# seed_sentinel.net
KiCad netlist of a schematic drawn in Altium Designer
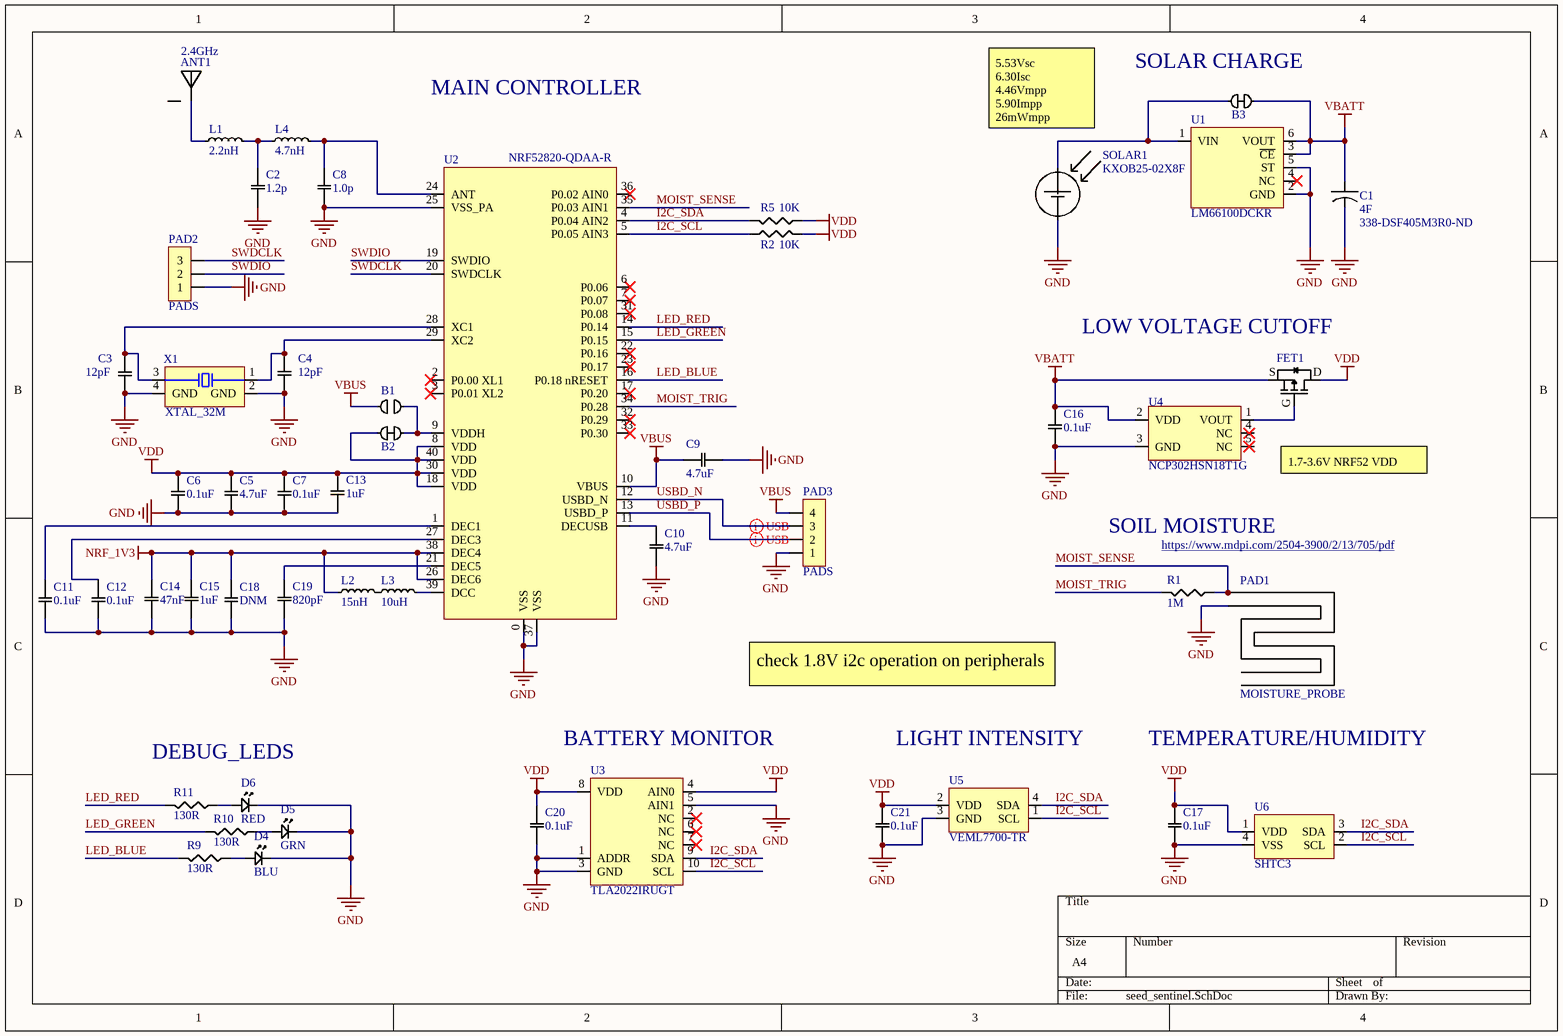
[diagram p0: seed_sentinel.SchDoc]

(export (version "E")
  (design (tool "Eeschema 10.0.6"))
  (components
    (comp (ref "ANT1")
      (value "2.4GHz")
      (footprint "ANT_RFANT5220110A2T")
      (description "2.4GHz chip antenna")
      (libsource (lib "seed_sentinel") (part "ANT_2G4_CHIP_RFANT5220110A2T"))
    )
    (comp (ref "B1")
      (value "SOLDER_BRIDGE_NO")
      (footprint "SOLDER_BRIDGE_NO")
      (libsource (lib "seed_sentinel") (part "SOLDER_BRIDGE_NO"))
    )
    (comp (ref "B2")
      (value "SOLDER_BRIDGE_C")
      (footprint "SOLDER_BRIDGE_NC")
      (libsource (lib "seed_sentinel") (part "SOLDER_BRIDGE_NC"))
    )
    (comp (ref "B3")
      (value "SOLDER_BRIDGE_C")
      (footprint "SOLDER_BRIDGE_NC")
      (libsource (lib "seed_sentinel") (part "SOLDER_BRIDGE_NC"))
    )
    (comp (ref "C1")
      (value "4F")
      (footprint "CAP_8mm")
      (description "4F 3V supercap")
      (fields (field (name "SUPPLIER PART NUMBER 1") "338-DSF405M3R0-ND"))
      (libsource (lib "seed_sentinel") (part "CAP_4_THRU"))
    )
    (comp (ref "C2")
      (value "1.2p")
      (footprint "CHIP_0402")
      (description "1.2pF RF capacitor")
      (libsource (lib "seed_sentinel") (part "CAP_1.2p_0402"))
    )
    (comp (ref "C3")
      (value "12pF")
      (footprint "CHIP_0402")
      (description "12pF NP0 0603 Capacitor")
      (libsource (lib "seed_sentinel") (part "CAP_12p_0402"))
    )
    (comp (ref "C4")
      (value "12pF")
      (footprint "CHIP_0402")
      (description "12pF NP0 0603 Capacitor")
      (libsource (lib "seed_sentinel") (part "CAP_12p_0402"))
    )
    (comp (ref "C5")
      (value "4.7uF")
      (footprint "CHIP_0402")
      (description "4.7uF 0603 6.3V")
      (libsource (lib "seed_sentinel") (part "CAP_4.7u_0402"))
    )
    (comp (ref "C6")
      (value "0.1uF")
      (footprint "CHIP_0402")
      (description "0.1uF X7R 0805 Capacitor")
      (libsource (lib "seed_sentinel") (part "CAP_100p_0402"))
    )
    (comp (ref "C7")
      (value "0.1uF")
      (footprint "CHIP_0402")
      (description "0.1uF X7R 0805 Capacitor")
      (libsource (lib "seed_sentinel") (part "CAP_100p_0402"))
    )
    (comp (ref "C8")
      (value "1.0p")
      (footprint "CHIP_0402")
      (description "1.0pF RF capacitor")
      (libsource (lib "seed_sentinel") (part "CAP_1.0p_0402"))
    )
    (comp (ref "C9")
      (value "4.7uF")
      (footprint "CHIP_0402")
      (description "4.7uF 0603 6.3V")
      (libsource (lib "seed_sentinel") (part "CAP_4.7u_0402"))
    )
    (comp (ref "C10")
      (value "4.7uF")
      (footprint "CHIP_0402")
      (description "4.7uF 0603 6.3V")
      (libsource (lib "seed_sentinel") (part "CAP_4.7u_0402"))
    )
    (comp (ref "C11")
      (value "0.1uF")
      (footprint "CHIP_0402")
      (description "0.1uF X7R 0805 Capacitor")
      (libsource (lib "seed_sentinel") (part "CAP_100p_0402"))
    )
    (comp (ref "C12")
      (value "0.1uF")
      (footprint "CHIP_0402")
      (description "0.1uF X7R 0805 Capacitor")
      (libsource (lib "seed_sentinel") (part "CAP_100p_0402"))
    )
    (comp (ref "C13")
      (value "1uF")
      (footprint "CHIP_0402")
      (libsource (lib "seed_sentinel") (part "CAP_1u_0402"))
    )
    (comp (ref "C14")
      (value "47nF")
      (footprint "CHIP_0402")
      (description "47nF 0603 6.3V")
      (libsource (lib "seed_sentinel") (part "CAP_47n_0402"))
    )
    (comp (ref "C15")
      (value "1uF")
      (footprint "CHIP_0402")
      (libsource (lib "seed_sentinel") (part "CAP_1u_0402"))
    )
    (comp (ref "C16")
      (value "0.1uF")
      (footprint "CHIP_0402")
      (description "0.1uF X7R 0805 Capacitor")
      (libsource (lib "seed_sentinel") (part "CAP_100p_0402"))
    )
    (comp (ref "C17")
      (value "0.1uF")
      (footprint "CHIP_0402")
      (description "0.1uF X7R 0805 Capacitor")
      (libsource (lib "seed_sentinel") (part "CAP_100p_0402"))
    )
    (comp (ref "C18")
      (value "DNM")
      (footprint "CHIP_0402")
      (libsource (lib "seed_sentinel") (part "CAP_DNM_0402"))
    )
    (comp (ref "C19")
      (value "820pF")
      (footprint "CHIP_0402")
      (description "820pF X7R 0805 Capacitor")
      (libsource (lib "seed_sentinel") (part "CAP_820p_0402"))
    )
    (comp (ref "C20")
      (value "0.1uF")
      (footprint "CHIP_0402")
      (description "0.1uF X7R 0805 Capacitor")
      (libsource (lib "seed_sentinel") (part "CAP_100p_0402"))
    )
    (comp (ref "C21")
      (value "0.1uF")
      (footprint "CHIP_0402")
      (description "0.1uF X7R 0805 Capacitor")
      (libsource (lib "seed_sentinel") (part "CAP_100p_0402"))
    )
    (comp (ref "D4")
      (value "BLU")
      (footprint "LED_0402")
      (libsource (lib "seed_sentinel") (part "LED_BLU_0402"))
    )
    (comp (ref "D5")
      (value "GRN")
      (footprint "LED_0402")
      (libsource (lib "seed_sentinel") (part "LED_GRN_0402"))
    )
    (comp (ref "D6")
      (value "RED")
      (footprint "LED_0402")
      (libsource (lib "seed_sentinel") (part "LED_RED_0402"))
    )
    (comp (ref "FET1")
      (value "RV2C014BCT2CL")
      (footprint "DFN1006-3")
      (libsource (lib "seed_sentinel") (part "FET_20V_200mA"))
    )
    (comp (ref "L1")
      (value "2.2nH")
      (footprint "CHIP_0402")
      (description "2.2nH high frequency")
      (libsource (lib "seed_sentinel") (part "IND_2.2n_0402"))
    )
    (comp (ref "L2")
      (value "15nH")
      (footprint "CHIP_0402")
      (description "15nH chip inductor")
      (libsource (lib "seed_sentinel") (part "IND_15n_0402"))
    )
    (comp (ref "L3")
      (value "10uH")
      (footprint "CHIP_0603")
      (description "10uH chip inductor")
      (libsource (lib "seed_sentinel") (part "IND_10u_0402"))
    )
    (comp (ref "L4")
      (value "4.7nH")
      (footprint "CHIP_0402")
      (description "4.7nH high frequency")
      (libsource (lib "seed_sentinel") (part "IND_4.7n_0402"))
    )
    (comp (ref "PAD1")
      (value "MOISTURE_PROBE")
      (footprint "MOIST_CAP")
      (libsource (lib "seed_sentinel") (part "MOISTURE_PROBE"))
    )
    (comp (ref "PAD2")
      (value "PADS")
      (footprint "CON_PADS_3")
      (libsource (lib "seed_sentinel") (part "CON_PADS_3"))
    )
    (comp (ref "PAD3")
      (value "PADS")
      (footprint "CON_PADS_4")
      (libsource (lib "seed_sentinel") (part "CON_PADS_4"))
    )
    (comp (ref "R1")
      (value "1M")
      (footprint "CHIP_0402")
      (description "1Mohm")
      (libsource (lib "seed_sentinel") (part "RES_1M_0402"))
    )
    (comp (ref "R2")
      (value "10K")
      (footprint "CHIP_0402")
      (description "10Kohm")
      (libsource (lib "seed_sentinel") (part "RES_10K_0402"))
    )
    (comp (ref "R5")
      (value "10K")
      (footprint "CHIP_0402")
      (description "10Kohm")
      (libsource (lib "seed_sentinel") (part "RES_10K_0402"))
    )
    (comp (ref "R9")
      (value "130R")
      (footprint "CHIP_0402")
      (description "130ohm")
      (libsource (lib "seed_sentinel") (part "RES_130R_0402"))
    )
    (comp (ref "R10")
      (value "130R")
      (footprint "CHIP_0402")
      (description "130ohm")
      (libsource (lib "seed_sentinel") (part "RES_130R_0402"))
    )
    (comp (ref "R11")
      (value "130R")
      (footprint "CHIP_0402")
      (description "130ohm")
      (libsource (lib "seed_sentinel") (part "RES_130R_0402"))
    )
    (comp (ref "SOLAR1")
      (value "KXOB25-02X8F")
      (footprint "SOLAR")
      (description "26.3mW 6.3mA 5.53V")
      (libsource (lib "seed_sentinel") (part "SOLAR_5V5_6m3"))
    )
    (comp (ref "U1")
      (value "LM66100DCKR")
      (footprint "SC70-6")
      (description "Ideal diode")
      (libsource (lib "seed_sentinel") (part "DIO_IDEAL"))
    )
    (comp (ref "U2")
      (value "NRF52820-QDAA-R")
      (footprint "QFN40 5x5")
      (libsource (lib "seed_sentinel") (part "NRF52820-QDAA-R"))
    )
    (comp (ref "U3")
      (value "TLA2022IRUGT")
      (footprint "RQFP_10")
      (libsource (lib "seed_sentinel") (part "SEN_ADC_TLA2022IRUGT"))
    )
    (comp (ref "U4")
      (value "NCP302HSN18T1G")
      (footprint "TSOP-5")
      (description "1.8V low voltage cutoff")
      (libsource (lib "seed_sentinel") (part "LVC_1.8V"))
    )
    (comp (ref "U5")
      (value "VEML7700-TR")
      (footprint "VEML7700")
      (libsource (lib "seed_sentinel") (part "SEN_LIGHT_VEML7700"))
    )
    (comp (ref "U6")
      (value "SHTC3")
      (footprint "SHTC3")
      (libsource (lib "seed_sentinel") (part "SEN_TEMP_HUMID_SHTC3"))
    )
    (comp (ref "X1")
      (value "XTAL_32M")
      (footprint "ECS-320")
      (libsource (lib "seed_sentinel") (part "XTAL_32M"))
    )
  )
  (nets
    (net (code "1") (name "/I2C_SCL") (class "Default")
      (node (ref "R2") (pin "1") (pinfunction "1_1") (pintype "passive"))
      (node (ref "U2") (pin "5") (pinfunction "P0.05_AIN3_5") (pintype "passive"))
      (node (ref "U3") (pin "10") (pinfunction "SCL_10") (pintype "passive"))
      (node (ref "U5") (pin "1") (pinfunction "SCL_1") (pintype "passive"))
      (node (ref "U6") (pin "2") (pinfunction "SCL_2") (pintype "passive"))
    )
    (net (code "2") (name "/I2C_SDA") (class "Default")
      (node (ref "R5") (pin "2") (pinfunction "2_2") (pintype "passive"))
      (node (ref "U2") (pin "4") (pinfunction "P0.04_AIN2_4") (pintype "passive"))
      (node (ref "U3") (pin "9") (pinfunction "SDA_9") (pintype "passive"))
      (node (ref "U5") (pin "4") (pinfunction "SDA_4") (pintype "passive"))
      (node (ref "U6") (pin "3") (pinfunction "SDA_3") (pintype "passive"))
    )
    (net (code "3") (name "/LED_BLUE") (class "Default")
      (node (ref "R9") (pin "2") (pinfunction "2_2") (pintype "passive"))
      (node (ref "U2") (pin "16") (pinfunction "P0.18_nRESET_16") (pintype "passive"))
    )
    (net (code "4") (name "/LED_GREEN") (class "Default")
      (node (ref "R10") (pin "2") (pinfunction "2_2") (pintype "passive"))
      (node (ref "U2") (pin "15") (pinfunction "P0.15_15") (pintype "passive"))
    )
    (net (code "5") (name "/LED_RED") (class "Default")
      (node (ref "R11") (pin "2") (pinfunction "2_2") (pintype "passive"))
      (node (ref "U2") (pin "14") (pinfunction "P0.14_14") (pintype "passive"))
    )
    (net (code "6") (name "/MOIST_SENSE") (class "Default")
      (node (ref "PAD1") (pin "1") (pinfunction "1_1") (pintype "passive"))
      (node (ref "R1") (pin "1") (pinfunction "1_1") (pintype "passive"))
      (node (ref "U2") (pin "35") (pinfunction "P0.03_AIN1_35") (pintype "passive"))
    )
    (net (code "7") (name "/MOIST_TRIG") (class "Default")
      (node (ref "R1") (pin "2") (pinfunction "2_2") (pintype "passive"))
      (node (ref "U2") (pin "34") (pinfunction "P0.28_34") (pintype "passive"))
    )
    (net (code "8") (name "/SWDCLK") (class "Default")
      (node (ref "PAD2") (pin "3") (pinfunction "3_3") (pintype "passive"))
      (node (ref "U2") (pin "20") (pinfunction "SWDCLK_20") (pintype "passive"))
    )
    (net (code "9") (name "/SWDIO") (class "Default")
      (node (ref "PAD2") (pin "2") (pinfunction "2_2") (pintype "passive"))
      (node (ref "U2") (pin "19") (pinfunction "SWDIO_19") (pintype "passive"))
    )
    (net (code "10") (name "/USBD_N") (class "Default")
      (node (ref "PAD3") (pin "3") (pinfunction "3_3") (pintype "passive"))
      (node (ref "U2") (pin "12") (pinfunction "USBD_N_12") (pintype "passive"))
    )
    (net (code "11") (name "/USBD_P") (class "Default")
      (node (ref "PAD3") (pin "2") (pinfunction "2_2") (pintype "passive"))
      (node (ref "U2") (pin "13") (pinfunction "USBD_P_13") (pintype "passive"))
    )
    (net (code "12") (name "GND") (class "Default")
      (node (ref "C1") (pin "-") (pinfunction "-_-") (pintype "passive"))
      (node (ref "C10") (pin "2") (pinfunction "2_2") (pintype "passive"))
      (node (ref "C11") (pin "2") (pinfunction "2_2") (pintype "passive"))
      (node (ref "C12") (pin "2") (pinfunction "2_2") (pintype "passive"))
      (node (ref "C13") (pin "1") (pinfunction "1_1") (pintype "passive"))
      (node (ref "C14") (pin "1") (pinfunction "1_1") (pintype "passive"))
      (node (ref "C15") (pin "1") (pinfunction "1_1") (pintype "passive"))
      (node (ref "C16") (pin "2") (pinfunction "2_2") (pintype "passive"))
      (node (ref "C17") (pin "2") (pinfunction "2_2") (pintype "passive"))
      (node (ref "C18") (pin "2") (pinfunction "2_2") (pintype "passive"))
      (node (ref "C19") (pin "1") (pinfunction "1_1") (pintype "passive"))
      (node (ref "C2") (pin "1") (pinfunction "1_1") (pintype "passive"))
      (node (ref "C20") (pin "2") (pinfunction "2_2") (pintype "passive"))
      (node (ref "C21") (pin "2") (pinfunction "2_2") (pintype "passive"))
      (node (ref "C3") (pin "2") (pinfunction "2_2") (pintype "passive"))
      (node (ref "C4") (pin "1") (pinfunction "1_1") (pintype "passive"))
      (node (ref "C5") (pin "2") (pinfunction "2_2") (pintype "passive"))
      (node (ref "C6") (pin "2") (pinfunction "2_2") (pintype "passive"))
      (node (ref "C7") (pin "2") (pinfunction "2_2") (pintype "passive"))
      (node (ref "C8") (pin "1") (pinfunction "1_1") (pintype "passive"))
      (node (ref "C9") (pin "2") (pinfunction "2_2") (pintype "passive"))
      (node (ref "D4") (pin "C") (pinfunction "C_C") (pintype "passive"))
      (node (ref "D5") (pin "C") (pinfunction "C_C") (pintype "passive"))
      (node (ref "D6") (pin "C") (pinfunction "C_C") (pintype "passive"))
      (node (ref "PAD1") (pin "2") (pinfunction "2_2") (pintype "passive"))
      (node (ref "PAD2") (pin "1") (pinfunction "1_1") (pintype "passive"))
      (node (ref "PAD3") (pin "1") (pinfunction "1_1") (pintype "passive"))
      (node (ref "SOLAR1") (pin "-") (pinfunction "-_-") (pintype "passive"))
      (node (ref "U1") (pin "2") (pinfunction "GND_2") (pintype "passive"))
      (node (ref "U1") (pin "5") (pinfunction "ST_5") (pintype "passive"))
      (node (ref "U2") (pin "0") (pinfunction "VSS_0") (pintype "passive"))
      (node (ref "U2") (pin "25") (pinfunction "VSS_PA_25") (pintype "passive"))
      (node (ref "U2") (pin "37") (pinfunction "VSS_37") (pintype "passive"))
      (node (ref "U3") (pin "1") (pinfunction "ADDR_1") (pintype "passive"))
      (node (ref "U3") (pin "3") (pinfunction "GND_3") (pintype "passive"))
      (node (ref "U3") (pin "5") (pinfunction "AIN1_5") (pintype "passive"))
      (node (ref "U4") (pin "3") (pinfunction "GND_3") (pintype "passive"))
      (node (ref "U5") (pin "3") (pinfunction "GND_3") (pintype "passive"))
      (node (ref "U6") (pin "4") (pinfunction "VSS_4") (pintype "passive"))
      (node (ref "X1") (pin "2") (pinfunction "GND_2") (pintype "passive"))
      (node (ref "X1") (pin "4") (pinfunction "GND_4") (pintype "passive"))
    )
    (net (code "13") (name "NRF_1V3") (class "Default")
      (node (ref "C14") (pin "2") (pinfunction "2_2") (pintype "passive"))
      (node (ref "C15") (pin "2") (pinfunction "2_2") (pintype "passive"))
      (node (ref "C18") (pin "1") (pinfunction "1_1") (pintype "passive"))
      (node (ref "L2") (pin "1") (pinfunction "1_1") (pintype "passive"))
      (node (ref "U2") (pin "26") (pinfunction "DEC6_26") (pintype "passive"))
      (node (ref "U2") (pin "38") (pinfunction "DEC4_38") (pintype "passive"))
    )
    (net (code "14") (name "Net-(ANT1-PadIN)") (class "Default")
      (node (ref "ANT1") (pin "IN") (pinfunction "IN_IN") (pintype "passive"))
      (node (ref "L1") (pin "1") (pinfunction "1_1") (pintype "passive"))
    )
    (net (code "15") (name "Net-(C2-Pad2)") (class "Default")
      (node (ref "C2") (pin "2") (pinfunction "2_2") (pintype "passive"))
      (node (ref "L1") (pin "2") (pinfunction "2_2") (pintype "passive"))
      (node (ref "L4") (pin "1") (pinfunction "1_1") (pintype "passive"))
    )
    (net (code "16") (name "Net-(D4-PadA)") (class "Default")
      (node (ref "D4") (pin "A") (pinfunction "A_A") (pintype "passive"))
      (node (ref "R9") (pin "1") (pinfunction "1_1") (pintype "passive"))
    )
    (net (code "17") (name "Net-(D5-PadA)") (class "Default")
      (node (ref "D5") (pin "A") (pinfunction "A_A") (pintype "passive"))
      (node (ref "R10") (pin "1") (pinfunction "1_1") (pintype "passive"))
    )
    (net (code "18") (name "Net-(D6-PadA)") (class "Default")
      (node (ref "D6") (pin "A") (pinfunction "A_A") (pintype "passive"))
      (node (ref "R11") (pin "1") (pinfunction "1_1") (pintype "passive"))
    )
    (net (code "19") (name "Net-(L2-Pad2)") (class "Default")
      (node (ref "L2") (pin "2") (pinfunction "2_2") (pintype "passive"))
      (node (ref "L3") (pin "1") (pinfunction "1_1") (pintype "passive"))
    )
    (net (code "20") (name "Net-(U1-VIN)") (class "Default")
      (node (ref "B3") (pin "1") (pinfunction "1_1") (pintype "passive"))
      (node (ref "SOLAR1") (pin "+") (pinfunction "+_+") (pintype "passive"))
      (node (ref "U1") (pin "1") (pinfunction "VIN_1") (pintype "passive"))
    )
    (net (code "21") (name "Net-(U2-ANT)") (class "Default")
      (node (ref "C8") (pin "2") (pinfunction "2_2") (pintype "passive"))
      (node (ref "L4") (pin "2") (pinfunction "2_2") (pintype "passive"))
      (node (ref "U2") (pin "24") (pinfunction "ANT_24") (pintype "passive"))
    )
    (net (code "22") (name "Net-(U2-DCC)") (class "Default")
      (node (ref "L3") (pin "2") (pinfunction "2_2") (pintype "passive"))
      (node (ref "U2") (pin "39") (pinfunction "DCC_39") (pintype "passive"))
    )
    (net (code "23") (name "Net-(U2-DEC1)") (class "Default")
      (node (ref "C11") (pin "1") (pinfunction "1_1") (pintype "passive"))
      (node (ref "U2") (pin "1") (pinfunction "DEC1_1") (pintype "passive"))
    )
    (net (code "24") (name "Net-(U2-DEC3)") (class "Default")
      (node (ref "C12") (pin "1") (pinfunction "1_1") (pintype "passive"))
      (node (ref "U2") (pin "27") (pinfunction "DEC3_27") (pintype "passive"))
    )
    (net (code "25") (name "Net-(U2-DEC5)") (class "Default")
      (node (ref "C19") (pin "2") (pinfunction "2_2") (pintype "passive"))
      (node (ref "U2") (pin "21") (pinfunction "DEC5_21") (pintype "passive"))
    )
    (net (code "26") (name "Net-(U2-DECUSB)") (class "Default")
      (node (ref "C10") (pin "1") (pinfunction "1_1") (pintype "passive"))
      (node (ref "U2") (pin "11") (pinfunction "DECUSB_11") (pintype "passive"))
    )
    (net (code "27") (name "Net-(U2-VDDH)") (class "Default")
      (node (ref "B1") (pin "1") (pinfunction "1_1") (pintype "passive"))
      (node (ref "B2") (pin "2") (pinfunction "2_2") (pintype "passive"))
      (node (ref "U2") (pin "9") (pinfunction "VDDH_9") (pintype "passive"))
    )
    (net (code "28") (name "Net-(U2-XC1)") (class "Default")
      (node (ref "C3") (pin "1") (pinfunction "1_1") (pintype "passive"))
      (node (ref "U2") (pin "28") (pinfunction "XC1_28") (pintype "passive"))
      (node (ref "X1") (pin "3") (pintype "passive"))
    )
    (net (code "29") (name "Net-(U2-XC2)") (class "Default")
      (node (ref "C4") (pin "2") (pinfunction "2_2") (pintype "passive"))
      (node (ref "U2") (pin "29") (pinfunction "XC2_29") (pintype "passive"))
      (node (ref "X1") (pin "1") (pintype "passive"))
    )
    (net (code "30") (name "Net-(U4-VOUT)") (class "Default")
      (node (ref "FET1") (pin "G") (pinfunction "G_G") (pintype "passive"))
      (node (ref "U4") (pin "1") (pinfunction "VOUT_1") (pintype "passive"))
    )
    (net (code "31") (name "VBATT") (class "Default")
      (node (ref "B3") (pin "2") (pinfunction "2_2") (pintype "passive"))
      (node (ref "C1") (pin "+") (pinfunction "+_+") (pintype "passive"))
      (node (ref "C16") (pin "1") (pinfunction "1_1") (pintype "passive"))
      (node (ref "FET1") (pin "S") (pinfunction "S_S") (pintype "passive"))
      (node (ref "U1") (pin "3") (pinfunction "~{CE}_3") (pintype "passive"))
      (node (ref "U1") (pin "6") (pinfunction "VOUT_6") (pintype "passive"))
      (node (ref "U4") (pin "2") (pinfunction "VDD_2") (pintype "passive"))
    )
    (net (code "32") (name "VBUS") (class "Default")
      (node (ref "B1") (pin "2") (pinfunction "2_2") (pintype "passive"))
      (node (ref "C9") (pin "1") (pinfunction "1_1") (pintype "passive"))
      (node (ref "PAD3") (pin "4") (pinfunction "4_4") (pintype "passive"))
      (node (ref "U2") (pin "10") (pinfunction "VBUS_10") (pintype "passive"))
    )
    (net (code "33") (name "VDD") (class "Default")
      (node (ref "B2") (pin "1") (pinfunction "1_1") (pintype "passive"))
      (node (ref "C13") (pin "2") (pinfunction "2_2") (pintype "passive"))
      (node (ref "C17") (pin "1") (pinfunction "1_1") (pintype "passive"))
      (node (ref "C20") (pin "1") (pinfunction "1_1") (pintype "passive"))
      (node (ref "C21") (pin "1") (pinfunction "1_1") (pintype "passive"))
      (node (ref "C5") (pin "1") (pinfunction "1_1") (pintype "passive"))
      (node (ref "C6") (pin "1") (pinfunction "1_1") (pintype "passive"))
      (node (ref "C7") (pin "1") (pinfunction "1_1") (pintype "passive"))
      (node (ref "FET1") (pin "D") (pinfunction "D_D") (pintype "passive"))
      (node (ref "R2") (pin "2") (pinfunction "2_2") (pintype "passive"))
      (node (ref "R5") (pin "1") (pinfunction "1_1") (pintype "passive"))
      (node (ref "U2") (pin "18") (pinfunction "VDD_18") (pintype "passive"))
      (node (ref "U2") (pin "30") (pinfunction "VDD_30") (pintype "passive"))
      (node (ref "U2") (pin "40") (pinfunction "VDD_40") (pintype "passive"))
      (node (ref "U2") (pin "8") (pinfunction "VDD_8") (pintype "passive"))
      (node (ref "U3") (pin "4") (pinfunction "AIN0_4") (pintype "passive"))
      (node (ref "U3") (pin "8") (pinfunction "VDD_8") (pintype "passive"))
      (node (ref "U5") (pin "2") (pinfunction "VDD_2") (pintype "passive"))
      (node (ref "U6") (pin "1") (pinfunction "VDD_1") (pintype "passive"))
    )
    (net (code "34") (name "unconnected-(ANT1-PadNC)") (class "Default")
      (node (ref "ANT1") (pin "NC") (pinfunction "NC_NC") (pintype "passive"))
    )
    (net (code "35") (name "unconnected-(U1-NC-Pad4)") (class "Default")
      (node (ref "U1") (pin "4") (pinfunction "NC_4") (pintype "passive+no_connect"))
    )
    (net (code "36") (name "unconnected-(U2-P0.00_XL1-Pad2)") (class "Default")
      (node (ref "U2") (pin "2") (pinfunction "P0.00_XL1_2") (pintype "passive+no_connect"))
    )
    (net (code "37") (name "unconnected-(U2-P0.01_XL2-Pad3)") (class "Default")
      (node (ref "U2") (pin "3") (pinfunction "P0.01_XL2_3") (pintype "passive+no_connect"))
    )
    (net (code "38") (name "unconnected-(U2-P0.02_AIN0-Pad36)") (class "Default")
      (node (ref "U2") (pin "36") (pinfunction "P0.02_AIN0_36") (pintype "passive+no_connect"))
    )
    (net (code "39") (name "unconnected-(U2-P0.06-Pad6)") (class "Default")
      (node (ref "U2") (pin "6") (pinfunction "P0.06_6") (pintype "passive+no_connect"))
    )
    (net (code "40") (name "unconnected-(U2-P0.07-Pad7)") (class "Default")
      (node (ref "U2") (pin "7") (pinfunction "P0.07_7") (pintype "passive+no_connect"))
    )
    (net (code "41") (name "unconnected-(U2-P0.08-Pad31)") (class "Default")
      (node (ref "U2") (pin "31") (pinfunction "P0.08_31") (pintype "passive+no_connect"))
    )
    (net (code "42") (name "unconnected-(U2-P0.16-Pad22)") (class "Default")
      (node (ref "U2") (pin "22") (pinfunction "P0.16_22") (pintype "passive+no_connect"))
    )
    (net (code "43") (name "unconnected-(U2-P0.17-Pad23)") (class "Default")
      (node (ref "U2") (pin "23") (pinfunction "P0.17_23") (pintype "passive+no_connect"))
    )
    (net (code "44") (name "unconnected-(U2-P0.20-Pad17)") (class "Default")
      (node (ref "U2") (pin "17") (pinfunction "P0.20_17") (pintype "passive+no_connect"))
    )
    (net (code "45") (name "unconnected-(U2-P0.29-Pad32)") (class "Default")
      (node (ref "U2") (pin "32") (pinfunction "P0.29_32") (pintype "passive+no_connect"))
    )
    (net (code "46") (name "unconnected-(U2-P0.30-Pad33)") (class "Default")
      (node (ref "U2") (pin "33") (pinfunction "P0.30_33") (pintype "passive+no_connect"))
    )
    (net (code "47") (name "unconnected-(U3-NC-Pad2)") (class "Default")
      (node (ref "U3") (pin "2") (pinfunction "NC_2") (pintype "passive+no_connect"))
    )
    (net (code "48") (name "unconnected-(U3-NC-Pad6)") (class "Default")
      (node (ref "U3") (pin "6") (pinfunction "NC_6") (pintype "passive+no_connect"))
    )
    (net (code "49") (name "unconnected-(U3-NC-Pad7)") (class "Default")
      (node (ref "U3") (pin "7") (pinfunction "NC_7") (pintype "passive+no_connect"))
    )
    (net (code "50") (name "unconnected-(U4-NC-Pad4)") (class "Default")
      (node (ref "U4") (pin "4") (pinfunction "NC_4") (pintype "passive"))
    )
    (net (code "51") (name "unconnected-(U4-NC-Pad5)") (class "Default")
      (node (ref "U4") (pin "5") (pinfunction "NC_5") (pintype "passive"))
    )
  )
)
